# SoundChip.net
KiCad netlist of a schematic drawn in Altium Designer
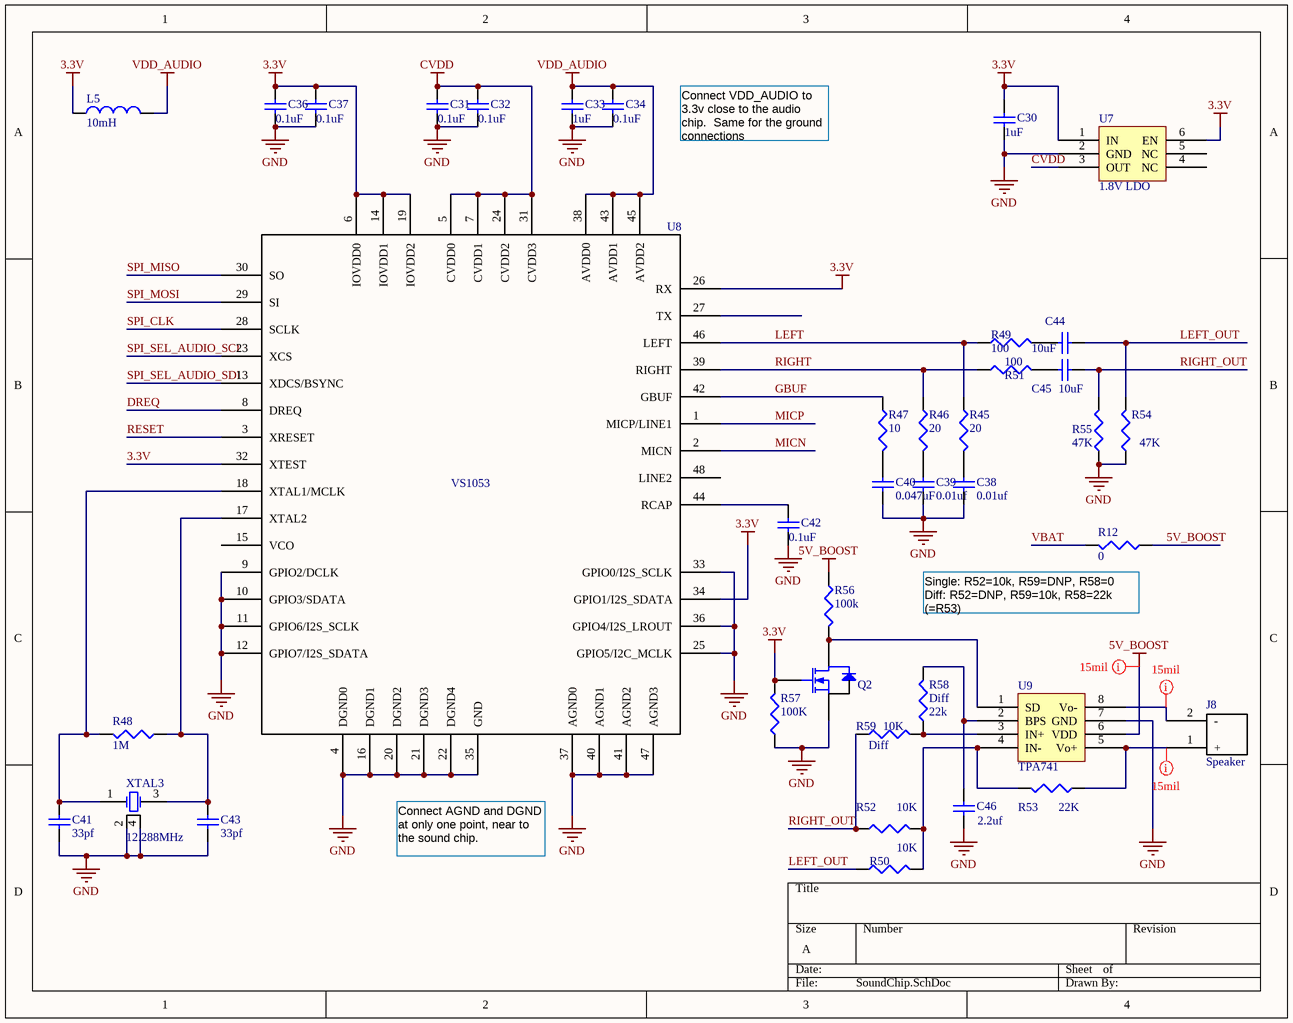
[diagram p0: SoundChip.SchDoc]

(export (version "E")
  (design (tool "Eeschema 10.0.6"))
  (components
    (comp (ref "C30")
      (value "1uF")
      (footprint "CAPC1608L")
      (description "Capacitor (Semiconductor SIM Model)")
      (fields (field (name "Comment") "Cap Semi") (field (name "PUBLISHER") "Altium Limited"))
      (libsource (lib "Miscellaneous Devices") (part "Cap Semi"))
    )
    (comp (ref "C31")
      (value "0.1uF")
      (footprint "CAPC1005L")
      (description "Capacitor (Semiconductor SIM Model)")
      (fields (field (name "Comment") "Cap Semi") (field (name "PUBLISHER") "Altium Limited"))
      (libsource (lib "Miscellaneous Devices") (part "Cap Semi"))
    )
    (comp (ref "C32")
      (value "0.1uF")
      (footprint "CAPC1005L")
      (description "Capacitor (Semiconductor SIM Model)")
      (fields (field (name "Comment") "Cap Semi") (field (name "PUBLISHER") "Altium Limited"))
      (libsource (lib "Miscellaneous Devices") (part "Cap Semi"))
    )
    (comp (ref "C33")
      (value "1uF")
      (footprint "CAPC1608L")
      (description "Capacitor (Semiconductor SIM Model)")
      (fields (field (name "Comment") "Cap Semi") (field (name "PUBLISHER") "Altium Limited"))
      (libsource (lib "Miscellaneous Devices") (part "Cap Semi"))
    )
    (comp (ref "C34")
      (value "0.1uF")
      (footprint "CAPC1005L")
      (description "Capacitor (Semiconductor SIM Model)")
      (fields (field (name "Comment") "Cap Semi") (field (name "PUBLISHER") "Altium Limited"))
      (libsource (lib "Miscellaneous Devices") (part "Cap Semi"))
    )
    (comp (ref "C36")
      (value "0.1uF")
      (footprint "CAPC1005L")
      (description "Capacitor (Semiconductor SIM Model)")
      (fields (field (name "Comment") "Cap Semi") (field (name "PUBLISHER") "Altium Limited"))
      (libsource (lib "Miscellaneous Devices") (part "Cap Semi"))
    )
    (comp (ref "C37")
      (value "0.1uF")
      (footprint "CAPC1005L")
      (description "Capacitor (Semiconductor SIM Model)")
      (fields (field (name "Comment") "Cap Semi") (field (name "PUBLISHER") "Altium Limited"))
      (libsource (lib "Miscellaneous Devices") (part "Cap Semi"))
    )
    (comp (ref "C38")
      (value "0.01uf")
      (footprint "CAPC1005L")
      (description "Capacitor (Semiconductor SIM Model)")
      (fields (field (name "Comment") "Cap Semi") (field (name "PUBLISHER") "Altium Limited"))
      (libsource (lib "Miscellaneous Devices") (part "Cap Semi"))
    )
    (comp (ref "C39")
      (value "0.01uf")
      (footprint "CAPC1005L")
      (description "Capacitor (Semiconductor SIM Model)")
      (fields (field (name "Comment") "Cap Semi") (field (name "PUBLISHER") "Altium Limited"))
      (libsource (lib "Miscellaneous Devices") (part "Cap Semi"))
    )
    (comp (ref "C40")
      (value "0.047uF")
      (footprint "CAPC1005L")
      (description "Capacitor (Semiconductor SIM Model)")
      (fields (field (name "Comment") "Cap Semi") (field (name "PUBLISHER") "Altium Limited"))
      (libsource (lib "Miscellaneous Devices") (part "Cap Semi"))
    )
    (comp (ref "C41")
      (value "33pf")
      (footprint "CAPC1005L")
      (description "Capacitor (Semiconductor SIM Model)")
      (fields (field (name "Comment") "Cap Semi") (field (name "PUBLISHER") "Altium Limited"))
      (libsource (lib "Miscellaneous Devices") (part "Cap Semi"))
    )
    (comp (ref "C42")
      (value "0.1uF")
      (footprint "CAPC1005L")
      (description "Capacitor (Semiconductor SIM Model)")
      (fields (field (name "Comment") "Cap Semi") (field (name "PUBLISHER") "Altium Limited"))
      (libsource (lib "Miscellaneous Devices") (part "Cap Semi"))
    )
    (comp (ref "C43")
      (value "33pf")
      (footprint "CAPC1005L")
      (description "Capacitor (Semiconductor SIM Model)")
      (fields (field (name "Comment") "Cap Semi") (field (name "PUBLISHER") "Altium Limited"))
      (libsource (lib "Miscellaneous Devices") (part "Cap Semi"))
    )
    (comp (ref "C44")
      (value "10uF")
      (footprint "CAPC1608L")
      (description "Capacitor (Semiconductor SIM Model)")
      (fields (field (name "Comment") "Cap Semi") (field (name "PUBLISHER") "Altium Limited"))
      (libsource (lib "Miscellaneous Devices") (part "Cap Semi"))
    )
    (comp (ref "C45")
      (value "10uF")
      (footprint "CAPC1608L")
      (description "Capacitor (Semiconductor SIM Model)")
      (fields (field (name "Comment") "Cap Semi") (field (name "PUBLISHER") "Altium Limited"))
      (libsource (lib "Miscellaneous Devices") (part "Cap Semi"))
    )
    (comp (ref "C46")
      (value "2.2uf")
      (footprint "CAPC1608L")
      (description "Capacitor (Semiconductor SIM Model)")
      (fields (field (name "Comment") "Cap Semi") (field (name "PUBLISHER") "Altium Limited"))
      (libsource (lib "Miscellaneous Devices") (part "Cap Semi"))
    )
    (comp (ref "J8")
      (value "Speaker")
      (footprint "BatteryConnJST")
      (libsource (lib "mrone") (part "BatteryConnJST"))
    )
    (comp (ref "L5")
      (value "10mH")
      (footprint "INDC2012L")
      (description "Inductor")
      (fields (field (name "PUBLISHER") "Altium Limited"))
      (libsource (lib "Miscellaneous Devices") (part "Inductor"))
    )
    (comp (ref "Q2") (value "Mosfet") (footprint "SOT-23") (libsource (lib "mrone") (part "Mosfet")))
    (comp (ref "R12")
      (value "0")
      (footprint "RESC1608L")
      (description "Resistor")
      (fields (field (name "Comment") "Res3") (field (name "PUBLISHER") "Altium Limited"))
      (libsource (lib "Miscellaneous Devices") (part "Res3"))
    )
    (comp (ref "R45")
      (value "20")
      (footprint "RESC1608L")
      (description "Resistor")
      (fields (field (name "Comment") "Res3") (field (name "PUBLISHER") "Altium Limited"))
      (libsource (lib "Miscellaneous Devices") (part "Res3"))
    )
    (comp (ref "R46")
      (value "20")
      (footprint "RESC1608L")
      (description "Resistor")
      (fields (field (name "Comment") "Res3") (field (name "PUBLISHER") "Altium Limited"))
      (libsource (lib "Miscellaneous Devices") (part "Res3"))
    )
    (comp (ref "R47")
      (value "10")
      (footprint "RESC1608L")
      (description "Resistor")
      (fields (field (name "Comment") "Res3") (field (name "PUBLISHER") "Altium Limited"))
      (libsource (lib "Miscellaneous Devices") (part "Res3"))
    )
    (comp (ref "R48")
      (value "1M")
      (footprint "RESC1608L")
      (description "Resistor")
      (fields (field (name "Comment") "Res3") (field (name "PUBLISHER") "Altium Limited"))
      (libsource (lib "Miscellaneous Devices") (part "Res3"))
    )
    (comp (ref "R49")
      (value "100")
      (footprint "RESC1608L")
      (description "Resistor")
      (fields (field (name "Comment") "Res3") (field (name "PUBLISHER") "Altium Limited"))
      (libsource (lib "Miscellaneous Devices") (part "Res3"))
    )
    (comp (ref "R50")
      (value "10K")
      (footprint "RESC1608L")
      (description "Resistor")
      (fields (field (name "Comment") "Res3") (field (name "PUBLISHER") "Altium Limited"))
      (libsource (lib "Miscellaneous Devices") (part "Res3"))
    )
    (comp (ref "R51")
      (value "100")
      (footprint "RESC1608L")
      (description "Resistor")
      (fields (field (name "Comment") "Res3") (field (name "PUBLISHER") "Altium Limited"))
      (libsource (lib "Miscellaneous Devices") (part "Res3"))
    )
    (comp (ref "R52")
      (value "10K")
      (footprint "RESC1608L")
      (description "Resistor")
      (fields (field (name "Comment") "Res3") (field (name "PUBLISHER") "Altium Limited"))
      (libsource (lib "Miscellaneous Devices") (part "Res3"))
    )
    (comp (ref "R53")
      (value "22K")
      (footprint "RESC1608L")
      (description "Resistor")
      (fields (field (name "Comment") "Res3") (field (name "PUBLISHER") "Altium Limited"))
      (libsource (lib "Miscellaneous Devices") (part "Res3"))
    )
    (comp (ref "R54")
      (value "47K")
      (footprint "RESC1608L")
      (description "Resistor")
      (fields (field (name "Comment") "Res3") (field (name "PUBLISHER") "Altium Limited"))
      (libsource (lib "Miscellaneous Devices") (part "Res3"))
    )
    (comp (ref "R55")
      (value "47K")
      (footprint "RESC1608L")
      (description "Resistor")
      (fields (field (name "Comment") "Res3") (field (name "PUBLISHER") "Altium Limited"))
      (libsource (lib "Miscellaneous Devices") (part "Res3"))
    )
    (comp (ref "R56")
      (value "100k")
      (footprint "RESC1608L")
      (description "Resistor")
      (fields (field (name "Comment") "Res3") (field (name "PUBLISHER") "Altium Limited"))
      (libsource (lib "Miscellaneous Devices") (part "Res3"))
    )
    (comp (ref "R57")
      (value "100K")
      (footprint "RESC1608L")
      (description "Resistor")
      (fields (field (name "Comment") "Res3") (field (name "PUBLISHER") "Altium Limited"))
      (libsource (lib "Miscellaneous Devices") (part "Res3"))
    )
    (comp (ref "R58")
      (value "Diff")
      (footprint "RESC1608L")
      (description "Resistor")
      (fields (field (name "ALTIUM_VALUE") "22k") (field (name "PUBLISHER") "Altium Limited"))
      (libsource (lib "Miscellaneous Devices") (part "Res3"))
    )
    (comp (ref "R59")
      (value "Diff")
      (footprint "RESC1608L")
      (description "Resistor")
      (fields (field (name "ALTIUM_VALUE") "10K") (field (name "PUBLISHER") "Altium Limited"))
      (libsource (lib "Miscellaneous Devices") (part "Res3"))
    )
    (comp (ref "U7") (value "1.8V LDO") (footprint "WFDFN-6") (libsource (lib "mrone") (part "1.8V_LDO")))
    (comp (ref "U8") (value "VS1053") (footprint "LQFP-48") (libsource (lib "mrone") (part "VS1053")))
    (comp (ref "U9")
      (value "TPA741")
      (footprint "audio amp")
      (libsource (lib "mrone") (part "Audio Amp TPA741"))
    )
    (comp (ref "XTAL3") (value "12.288MHz") (footprint "CRYSTAL") (libsource (lib "mrone") (part "Crystal")))
  )
  (nets
    (net (code "1") (name "/DREQ") (class "Default")
      (node (ref "U8") (pin "8") (pinfunction "DREQ_8") (pintype "passive"))
    )
    (net (code "2") (name "/GBUF") (class "Default")
      (node (ref "R47") (pin "1") (pinfunction "1_1") (pintype "passive"))
      (node (ref "U8") (pin "42") (pinfunction "GBUF_42") (pintype "passive"))
    )
    (net (code "3") (name "/LEFT") (class "Default")
      (node (ref "R45") (pin "1") (pinfunction "1_1") (pintype "passive"))
      (node (ref "R49") (pin "1") (pinfunction "1_1") (pintype "passive"))
      (node (ref "U8") (pin "46") (pinfunction "LEFT_46") (pintype "passive"))
    )
    (net (code "4") (name "/LEFT_OUT") (class "Default")
      (node (ref "C44") (pin "1") (pinfunction "1_1") (pintype "passive"))
      (node (ref "R50") (pin "1") (pinfunction "1_1") (pintype "passive"))
      (node (ref "R54") (pin "2") (pinfunction "2_2") (pintype "passive"))
    )
    (net (code "5") (name "/MICN") (class "Default")
      (node (ref "U8") (pin "2") (pinfunction "MICN_2") (pintype "passive"))
    )
    (net (code "6") (name "/MICP") (class "Default")
      (node (ref "U8") (pin "1") (pinfunction "MICP/LINE1_1") (pintype "passive"))
    )
    (net (code "7") (name "/RESET") (class "Default")
      (node (ref "U8") (pin "3") (pinfunction "XRESET_3") (pintype "passive"))
    )
    (net (code "8") (name "/RIGHT") (class "Default")
      (node (ref "R46") (pin "1") (pinfunction "1_1") (pintype "passive"))
      (node (ref "R51") (pin "1") (pinfunction "1_1") (pintype "passive"))
      (node (ref "U8") (pin "39") (pinfunction "RIGHT_39") (pintype "passive"))
    )
    (net (code "9") (name "/RIGHT_OUT") (class "Default")
      (node (ref "C45") (pin "1") (pinfunction "1_1") (pintype "passive"))
      (node (ref "R52") (pin "1") (pinfunction "1_1") (pintype "passive"))
      (node (ref "R55") (pin "2") (pinfunction "2_2") (pintype "passive"))
      (node (ref "R59") (pin "1") (pinfunction "1_1") (pintype "passive"))
    )
    (net (code "10") (name "/SPI_CLK") (class "Default")
      (node (ref "U8") (pin "28") (pinfunction "SCLK_28") (pintype "passive"))
    )
    (net (code "11") (name "/SPI_MISO") (class "Default")
      (node (ref "U8") (pin "30") (pinfunction "SO_30") (pintype "passive"))
    )
    (net (code "12") (name "/SPI_MOSI") (class "Default")
      (node (ref "U8") (pin "29") (pinfunction "SI_29") (pintype "passive"))
    )
    (net (code "13") (name "/SPI_SEL_AUDIO_SCI") (class "Default")
      (node (ref "U8") (pin "23") (pinfunction "XCS_23") (pintype "passive"))
    )
    (net (code "14") (name "/SPI_SEL_AUDIO_SDI") (class "Default")
      (node (ref "U8") (pin "13") (pinfunction "XDCS/BSYNC_13") (pintype "passive"))
    )
    (net (code "15") (name "/VBAT") (class "Default")
      (node (ref "R12") (pin "2") (pinfunction "2_2") (pintype "passive"))
    )
    (net (code "16") (name "3.3V") (class "Default")
      (node (ref "C30") (pin "1") (pinfunction "1_1") (pintype "passive"))
      (node (ref "C36") (pin "2") (pinfunction "2_2") (pintype "passive"))
      (node (ref "C37") (pin "2") (pinfunction "2_2") (pintype "passive"))
      (node (ref "L5") (pin "2") (pinfunction "2_2") (pintype "passive"))
      (node (ref "Q2") (pin "1") (pinfunction "G_1") (pintype "passive"))
      (node (ref "R57") (pin "2") (pinfunction "2_2") (pintype "passive"))
      (node (ref "U7") (pin "1") (pinfunction "IN_1") (pintype "passive"))
      (node (ref "U7") (pin "6") (pinfunction "EN_6") (pintype "passive"))
      (node (ref "U8") (pin "14") (pinfunction "IOVDD1_14") (pintype "passive"))
      (node (ref "U8") (pin "19") (pinfunction "IOVDD2_19") (pintype "passive"))
      (node (ref "U8") (pin "26") (pinfunction "RX_26") (pintype "passive"))
      (node (ref "U8") (pin "32") (pinfunction "XTEST_32") (pintype "passive"))
      (node (ref "U8") (pin "34") (pinfunction "GPIO1/I2S_SDATA_34") (pintype "passive"))
      (node (ref "U8") (pin "6") (pinfunction "IOVDD0_6") (pintype "passive"))
    )
    (net (code "17") (name "5V_BOOST") (class "Default")
      (node (ref "R12") (pin "1") (pinfunction "1_1") (pintype "passive"))
      (node (ref "R56") (pin "2") (pinfunction "2_2") (pintype "passive"))
      (node (ref "U9") (pin "6") (pinfunction "VDD_6") (pintype "passive"))
    )
    (net (code "18") (name "CVDD") (class "Default")
      (node (ref "C31") (pin "2") (pinfunction "2_2") (pintype "passive"))
      (node (ref "C32") (pin "2") (pinfunction "2_2") (pintype "passive"))
      (node (ref "U7") (pin "3") (pinfunction "OUT_3") (pintype "passive"))
      (node (ref "U8") (pin "24") (pinfunction "CVDD2_24") (pintype "passive"))
      (node (ref "U8") (pin "31") (pinfunction "CVDD3_31") (pintype "passive"))
      (node (ref "U8") (pin "5") (pinfunction "CVDD0_5") (pintype "passive"))
      (node (ref "U8") (pin "7") (pinfunction "CVDD1_7") (pintype "passive"))
    )
    (net (code "19") (name "GND") (class "Default")
      (node (ref "C30") (pin "2") (pinfunction "2_2") (pintype "passive"))
      (node (ref "C31") (pin "1") (pinfunction "1_1") (pintype "passive"))
      (node (ref "C32") (pin "1") (pinfunction "1_1") (pintype "passive"))
      (node (ref "C33") (pin "2") (pinfunction "2_2") (pintype "passive"))
      (node (ref "C34") (pin "1") (pinfunction "1_1") (pintype "passive"))
      (node (ref "C36") (pin "1") (pinfunction "1_1") (pintype "passive"))
      (node (ref "C37") (pin "1") (pinfunction "1_1") (pintype "passive"))
      (node (ref "C38") (pin "2") (pinfunction "2_2") (pintype "passive"))
      (node (ref "C39") (pin "2") (pinfunction "2_2") (pintype "passive"))
      (node (ref "C40") (pin "2") (pinfunction "2_2") (pintype "passive"))
      (node (ref "C41") (pin "2") (pinfunction "2_2") (pintype "passive"))
      (node (ref "C42") (pin "1") (pinfunction "1_1") (pintype "passive"))
      (node (ref "C43") (pin "2") (pinfunction "2_2") (pintype "passive"))
      (node (ref "C46") (pin "1") (pinfunction "1_1") (pintype "passive"))
      (node (ref "Q2") (pin "2") (pinfunction "S_2") (pintype "passive"))
      (node (ref "R54") (pin "1") (pinfunction "1_1") (pintype "passive"))
      (node (ref "R55") (pin "1") (pinfunction "1_1") (pintype "passive"))
      (node (ref "R57") (pin "1") (pinfunction "1_1") (pintype "passive"))
      (node (ref "U7") (pin "2") (pinfunction "GND_2") (pintype "passive"))
      (node (ref "U8") (pin "10") (pinfunction "GPIO3/SDATA_10") (pintype "passive"))
      (node (ref "U8") (pin "11") (pinfunction "GPIO6/I2S_SCLK_11") (pintype "passive"))
      (node (ref "U8") (pin "12") (pinfunction "GPIO7/I2S_SDATA_12") (pintype "passive"))
      (node (ref "U8") (pin "16") (pinfunction "DGND1_16") (pintype "passive"))
      (node (ref "U8") (pin "20") (pinfunction "DGND2_20") (pintype "passive"))
      (node (ref "U8") (pin "21") (pinfunction "DGND3_21") (pintype "passive"))
      (node (ref "U8") (pin "22") (pinfunction "DGND4_22") (pintype "passive"))
      (node (ref "U8") (pin "25") (pinfunction "GPIO5/I2C_MCLK_25") (pintype "passive"))
      (node (ref "U8") (pin "33") (pinfunction "GPIO0/I2S_SCLK_33") (pintype "passive"))
      (node (ref "U8") (pin "35") (pinfunction "GND_35") (pintype "passive"))
      (node (ref "U8") (pin "36") (pinfunction "GPIO4/I2S_LROUT_36") (pintype "passive"))
      (node (ref "U8") (pin "37") (pinfunction "AGND0_37") (pintype "passive"))
      (node (ref "U8") (pin "4") (pinfunction "DGND0_4") (pintype "passive"))
      (node (ref "U8") (pin "40") (pinfunction "AGND1_40") (pintype "passive"))
      (node (ref "U8") (pin "41") (pinfunction "AGND2_41") (pintype "passive"))
      (node (ref "U8") (pin "47") (pinfunction "AGND3_47") (pintype "passive"))
      (node (ref "U8") (pin "9") (pinfunction "GPIO2/DCLK_9") (pintype "passive"))
      (node (ref "U9") (pin "7") (pinfunction "GND_7") (pintype "passive"))
      (node (ref "XTAL3") (pin "2") (pinfunction "GND_2") (pintype "passive"))
      (node (ref "XTAL3") (pin "4") (pinfunction "GND_4") (pintype "passive"))
    )
    (net (code "20") (name "Net-(C38-Pad1)") (class "Default")
      (node (ref "C38") (pin "1") (pinfunction "1_1") (pintype "passive"))
      (node (ref "R45") (pin "2") (pinfunction "2_2") (pintype "passive"))
    )
    (net (code "21") (name "Net-(C39-Pad1)") (class "Default")
      (node (ref "C39") (pin "1") (pinfunction "1_1") (pintype "passive"))
      (node (ref "R46") (pin "2") (pinfunction "2_2") (pintype "passive"))
    )
    (net (code "22") (name "Net-(C40-Pad1)") (class "Default")
      (node (ref "C40") (pin "1") (pinfunction "1_1") (pintype "passive"))
      (node (ref "R47") (pin "2") (pinfunction "2_2") (pintype "passive"))
    )
    (net (code "23") (name "Net-(C44-Pad2)") (class "Default")
      (node (ref "C44") (pin "2") (pinfunction "2_2") (pintype "passive"))
      (node (ref "R49") (pin "2") (pinfunction "2_2") (pintype "passive"))
    )
    (net (code "24") (name "Net-(C45-Pad2)") (class "Default")
      (node (ref "C45") (pin "2") (pinfunction "2_2") (pintype "passive"))
      (node (ref "R51") (pin "2") (pinfunction "2_2") (pintype "passive"))
    )
    (net (code "25") (name "Net-(J8-+)") (class "Default")
      (node (ref "J8") (pin "1") (pinfunction "+_1") (pintype "passive"))
      (node (ref "R53") (pin "1") (pinfunction "1_1") (pintype "passive"))
      (node (ref "U9") (pin "5") (pinfunction "Vo+_5") (pintype "passive"))
    )
    (net (code "26") (name "Net-(J8--)") (class "Default")
      (node (ref "J8") (pin "2") (pinfunction "-_2") (pintype "passive"))
      (node (ref "U9") (pin "8") (pinfunction "Vo-_8") (pintype "passive"))
    )
    (net (code "27") (name "Net-(Q2-D)") (class "Default")
      (node (ref "Q2") (pin "3") (pinfunction "D_3") (pintype "passive"))
      (node (ref "R56") (pin "1") (pinfunction "1_1") (pintype "passive"))
      (node (ref "U9") (pin "1") (pinfunction "SD_1") (pintype "passive"))
    )
    (net (code "28") (name "Net-(U8-RCAP)") (class "Default")
      (node (ref "C42") (pin "2") (pinfunction "2_2") (pintype "passive"))
      (node (ref "U8") (pin "44") (pinfunction "RCAP_44") (pintype "passive"))
    )
    (net (code "29") (name "Net-(U8-XTAL1{slash}MCLK)") (class "Default")
      (node (ref "C41") (pin "1") (pinfunction "1_1") (pintype "passive"))
      (node (ref "R48") (pin "2") (pinfunction "2_2") (pintype "passive"))
      (node (ref "U8") (pin "18") (pinfunction "XTAL1/MCLK_18") (pintype "passive"))
      (node (ref "XTAL3") (pin "1") (pinfunction "OSC1_1") (pintype "passive"))
    )
    (net (code "30") (name "Net-(U8-XTAL2)") (class "Default")
      (node (ref "C43") (pin "1") (pinfunction "1_1") (pintype "passive"))
      (node (ref "R48") (pin "1") (pinfunction "1_1") (pintype "passive"))
      (node (ref "U8") (pin "17") (pinfunction "XTAL2_17") (pintype "passive"))
      (node (ref "XTAL3") (pin "3") (pinfunction "OSC2_3") (pintype "passive"))
    )
    (net (code "31") (name "Net-(U9-BPS)") (class "Default")
      (node (ref "C46") (pin "2") (pinfunction "2_2") (pintype "passive"))
      (node (ref "R58") (pin "2") (pinfunction "2_2") (pintype "passive"))
      (node (ref "U9") (pin "2") (pinfunction "BPS_2") (pintype "passive"))
    )
    (net (code "32") (name "Net-(U9-IN+)") (class "Default")
      (node (ref "R58") (pin "1") (pinfunction "1_1") (pintype "passive"))
      (node (ref "R59") (pin "2") (pinfunction "2_2") (pintype "passive"))
      (node (ref "U9") (pin "3") (pinfunction "IN+_3") (pintype "passive"))
    )
    (net (code "33") (name "Net-(U9-IN-)") (class "Default")
      (node (ref "R50") (pin "2") (pinfunction "2_2") (pintype "passive"))
      (node (ref "R52") (pin "2") (pinfunction "2_2") (pintype "passive"))
      (node (ref "R53") (pin "2") (pinfunction "2_2") (pintype "passive"))
      (node (ref "U9") (pin "4") (pinfunction "IN-_4") (pintype "passive"))
    )
    (net (code "34") (name "VDD_AUDIO") (class "Default")
      (node (ref "C33") (pin "1") (pinfunction "1_1") (pintype "passive"))
      (node (ref "C34") (pin "2") (pinfunction "2_2") (pintype "passive"))
      (node (ref "L5") (pin "1") (pinfunction "1_1") (pintype "passive"))
      (node (ref "U8") (pin "38") (pinfunction "AVDD0_38") (pintype "passive"))
      (node (ref "U8") (pin "43") (pinfunction "AVDD1_43") (pintype "passive"))
      (node (ref "U8") (pin "45") (pinfunction "AVDD2_45") (pintype "passive"))
    )
    (net (code "35") (name "unconnected-(U7-NC-Pad4)") (class "Default")
      (node (ref "U7") (pin "4") (pinfunction "NC_4") (pintype "passive"))
    )
    (net (code "36") (name "unconnected-(U7-NC-Pad5)") (class "Default")
      (node (ref "U7") (pin "5") (pinfunction "NC_5") (pintype "passive"))
    )
    (net (code "37") (name "unconnected-(U8-LINE2-Pad48)") (class "Default")
      (node (ref "U8") (pin "48") (pinfunction "LINE2_48") (pintype "passive"))
    )
    (net (code "38") (name "unconnected-(U8-TX-Pad27)") (class "Default")
      (node (ref "U8") (pin "27") (pinfunction "TX_27") (pintype "passive"))
    )
    (net (code "39") (name "unconnected-(U8-VCO-Pad15)") (class "Default")
      (node (ref "U8") (pin "15") (pinfunction "VCO_15") (pintype "passive"))
    )
  )
)
